# transmitter_SI5351_Arduinol.net
KiCad netlist of a schematic drawn in EAGLE
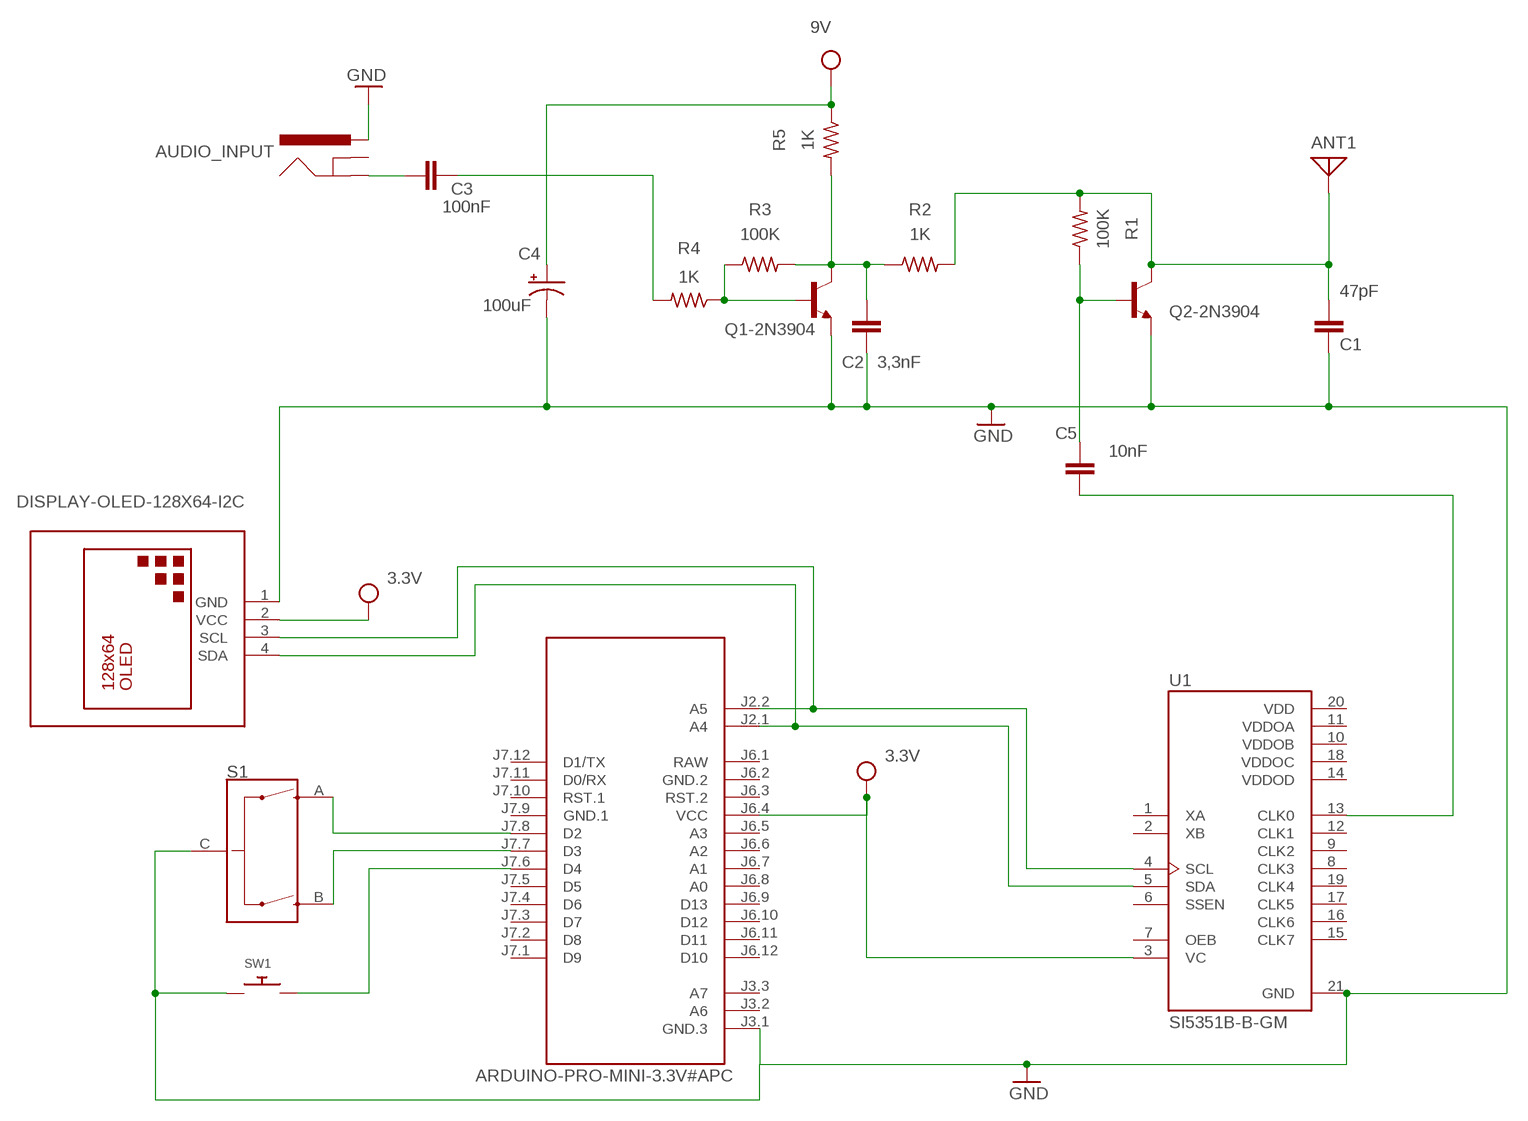
[diagram p0: schematic, sheet 1]

(export (version "E")
  (design (tool "Eeschema 10.0.6"))
  (components
    (comp (ref "ANT1")
      (value "ANTENNA")
      (footprint "eagle-import:PAD-01")
      (libsource (lib "eagle-import") (part "ANTENNA"))
    )
    (comp (ref "AUDIO_INPUT")
      (value "POWER_JACKPTH_SMD_COMBO")
      (footprint "eagle-import:POWER_JACK_COMBO")
      (libsource (lib "eagle-import") (part "POWER_JACKPTH_SMD_COMBO"))
    )
    (comp (ref "C1")
      (value "47pF")
      (footprint "eagle-import:XC10B6")
      (libsource (lib "eagle-import") (part "CXXC10B6"))
    )
    (comp (ref "C2")
      (value "3,3nF")
      (footprint "eagle-import:XC10B6")
      (libsource (lib "eagle-import") (part "CXXC10B6"))
    )
    (comp (ref "C3")
      (value "100nF")
      (footprint "eagle-import:XC10B6")
      (libsource (lib "eagle-import") (part "CXXC10B6"))
    )
    (comp (ref "C4")
      (value "100uF")
      (footprint "eagle-import:NIC_10X10.5_CAP")
      (libsource (lib "eagle-import") (part "100UF-POLAR-10X10.5-63V-20%"))
    )
    (comp (ref "C5")
      (value "10nF")
      (footprint "eagle-import:XC10B6")
      (libsource (lib "eagle-import") (part "CXXC10B6"))
    )
    (comp (ref "M2")
      (value "ARDUINO-PRO-MINI-3.3V#APC")
      (footprint "eagle-import:ARDUINO-PRO-MINI#APC")
      (libsource (lib "eagle-import") (part "ARDUINO-PRO-MINI-#APC3.3V"))
    )
    (comp (ref "Q1-2N3904")
      (value "200mA/40V")
      (footprint "eagle-import:TO-92")
      (libsource (lib "eagle-import") (part "TRANS_NPN-2N3904"))
    )
    (comp (ref "Q2-2N3904")
      (value "200mA/40V")
      (footprint "eagle-import:TO-92")
      (libsource (lib "eagle-import") (part "TRANS_NPN-2N3904"))
    )
    (comp (ref "R1")
      (value "100K")
      (footprint "eagle-import:RESAD724W46L381D178B")
      (libsource (lib "eagle-import") (part "R-USAXIAL-7.2MM-PITCH_"))
    )
    (comp (ref "R2")
      (value "1K")
      (footprint "eagle-import:RESAD724W46L381D178B")
      (libsource (lib "eagle-import") (part "R-USAXIAL-7.2MM-PITCH_"))
    )
    (comp (ref "R3")
      (value "100K")
      (footprint "eagle-import:RESAD724W46L381D178B")
      (libsource (lib "eagle-import") (part "R-USAXIAL-7.2MM-PITCH_"))
    )
    (comp (ref "R4")
      (value "1K")
      (footprint "eagle-import:RESAD724W46L381D178B")
      (libsource (lib "eagle-import") (part "R-USAXIAL-7.2MM-PITCH_"))
    )
    (comp (ref "R5")
      (value "1K")
      (footprint "eagle-import:RESAD724W46L381D178B")
      (libsource (lib "eagle-import") (part "R-USAXIAL-7.2MM-PITCH_"))
    )
    (comp (ref "S1")
      (value "ENCODER")
      (footprint "eagle-import:ENCODER-16MM-QUAD")
      (libsource (lib "eagle-import") (part "ENCODER"))
    )
    (comp (ref "SW1")
      (value "SWITCH_PUSHBUTTONC&K_KSS")
      (footprint "eagle-import:BTN_CK_KSS")
      (libsource (lib "eagle-import") (part "SWITCH_PUSHBUTTONC&K_KSS"))
    )
    (comp (ref "U$2")
      (value "DISPLAY-OLED-128X64-I2C")
      (footprint "eagle-import:DISPLAY-OLED-128X64-I2C")
      (libsource (lib "eagle-import") (part "DISPLAY-OLED-128X64-I2C"))
    )
    (comp (ref "U1")
      (value "SI5351B-B-GM")
      (footprint "eagle-import:QFN50P400X400X90-21N")
      (fields (field (name "MF") "Silicon Labs"))
      (libsource (lib "eagle-import") (part "SI5351B-B-GM"))
    )
  )
  (nets
    (net (code "1") (name "/GND.1") (class "Default")
      (node (ref "M2") (pin "J7.9") (pinfunction "GND.1_J7.9") (pintype "power_in"))
    )
    (net (code "2") (name "/GND.2") (class "Default")
      (node (ref "M2") (pin "J6.2") (pinfunction "GND.2_J6.2") (pintype "power_in"))
    )
    (net (code "3") (name "/RAW") (class "Default")
      (node (ref "M2") (pin "J6.1") (pinfunction "RAW_J6.1") (pintype "power_in"))
    )
    (net (code "4") (name "/VDD") (class "Default")
      (node (ref "U1") (pin "20") (pinfunction "VDD_20") (pintype "power_in"))
    )
    (net (code "5") (name "/VDDOA") (class "Default")
      (node (ref "U1") (pin "11") (pinfunction "VDDOA_11") (pintype "power_in"))
    )
    (net (code "6") (name "/VDDOB") (class "Default")
      (node (ref "U1") (pin "10") (pinfunction "VDDOB_10") (pintype "power_in"))
    )
    (net (code "7") (name "/VDDOC") (class "Default")
      (node (ref "U1") (pin "18") (pinfunction "VDDOC_18") (pintype "power_in"))
    )
    (net (code "8") (name "/VDDOD") (class "Default")
      (node (ref "U1") (pin "14") (pinfunction "VDDOD_14") (pintype "power_in"))
    )
    (net (code "9") (name "GND") (class "Default")
      (node (ref "AUDIO_INPUT") (pin "POWER") (pinfunction "PWR_POWER") (pintype "bidirectional"))
      (node (ref "C1") (pin "2") (pinfunction "2_2") (pintype "passive"))
      (node (ref "C2") (pin "2") (pinfunction "2_2") (pintype "passive"))
      (node (ref "C4") (pin "-") (pinfunction "-_-") (pintype "passive"))
      (node (ref "M2") (pin "J3.1") (pinfunction "GND.3_J3.1") (pintype "bidirectional"))
      (node (ref "Q1-2N3904") (pin "1") (pinfunction "E_1") (pintype "passive"))
      (node (ref "Q2-2N3904") (pin "1") (pinfunction "E_1") (pintype "passive"))
      (node (ref "S1") (pin "C") (pinfunction "C_C") (pintype "bidirectional"))
      (node (ref "SW1") (pin "P$1") (pinfunction "P$1_P$1") (pintype "passive"))
      (node (ref "U$2") (pin "1") (pinfunction "GND_1") (pintype "power_in"))
      (node (ref "U1") (pin "21") (pinfunction "GND_21") (pintype "power_in"))
    )
    (net (code "10") (name "Net-(AUDIO_INPUT-GND)") (class "Default")
      (node (ref "AUDIO_INPUT") (pin "GND@1") (pinfunction "GND_GND@1") (pintype "bidirectional"))
      (node (ref "C3") (pin "1") (pinfunction "1_1") (pintype "passive"))
    )
    (net (code "11") (name "Net-(C3-Pad2)") (class "Default")
      (node (ref "C3") (pin "2") (pinfunction "2_2") (pintype "passive"))
      (node (ref "R4") (pin "2") (pinfunction "2_2") (pintype "passive"))
    )
    (net (code "12") (name "Net-(M2-A4)") (class "Default")
      (node (ref "M2") (pin "J2.1") (pinfunction "A4_J2.1") (pintype "bidirectional"))
      (node (ref "U$2") (pin "4") (pinfunction "SDA_4") (pintype "bidirectional"))
      (node (ref "U1") (pin "5") (pinfunction "SDA_5") (pintype "bidirectional"))
    )
    (net (code "13") (name "Net-(M2-A5)") (class "Default")
      (node (ref "M2") (pin "J2.2") (pinfunction "A5_J2.2") (pintype "bidirectional"))
      (node (ref "U$2") (pin "3") (pinfunction "SCL_3") (pintype "bidirectional"))
      (node (ref "U1") (pin "4") (pinfunction "SCL_4") (pintype "input"))
    )
    (net (code "14") (name "Net-(M2-D2)") (class "Default")
      (node (ref "M2") (pin "J7.8") (pinfunction "D2_J7.8") (pintype "bidirectional"))
      (node (ref "S1") (pin "A") (pinfunction "A_A") (pintype "bidirectional"))
    )
    (net (code "15") (name "Net-(M2-D3)") (class "Default")
      (node (ref "M2") (pin "J7.7") (pinfunction "D3_J7.7") (pintype "bidirectional"))
      (node (ref "S1") (pin "B") (pinfunction "B_B") (pintype "bidirectional"))
    )
    (net (code "16") (name "Net-(M2-D4)") (class "Default")
      (node (ref "M2") (pin "J7.6") (pinfunction "D4_J7.6") (pintype "bidirectional"))
      (node (ref "SW1") (pin "P$2") (pinfunction "P$2_P$2") (pintype "passive"))
    )
    (net (code "17") (name "Net-(Q1-2N3904-B)") (class "Default")
      (node (ref "Q1-2N3904") (pin "2") (pinfunction "B_2") (pintype "passive"))
      (node (ref "R3") (pin "1") (pinfunction "1_1") (pintype "passive"))
      (node (ref "R4") (pin "1") (pinfunction "1_1") (pintype "passive"))
    )
    (net (code "18") (name "Net-(Q1-2N3904-C)") (class "Default")
      (node (ref "C2") (pin "1") (pinfunction "1_1") (pintype "passive"))
      (node (ref "Q1-2N3904") (pin "3") (pinfunction "C_3") (pintype "passive"))
      (node (ref "R2") (pin "1") (pinfunction "1_1") (pintype "passive"))
      (node (ref "R3") (pin "2") (pinfunction "2_2") (pintype "passive"))
      (node (ref "R5") (pin "2") (pinfunction "2_2") (pintype "passive"))
    )
    (net (code "19") (name "Net-(Q2-2N3904-B)") (class "Default")
      (node (ref "C5") (pin "1") (pinfunction "1_1") (pintype "passive"))
      (node (ref "Q2-2N3904") (pin "2") (pinfunction "B_2") (pintype "passive"))
      (node (ref "R1") (pin "1") (pinfunction "1_1") (pintype "passive"))
    )
    (net (code "20") (name "Net-(Q2-2N3904-C)") (class "Default")
      (node (ref "ANT1") (pin "1") (pinfunction "1_1") (pintype "output"))
      (node (ref "C1") (pin "1") (pinfunction "1_1") (pintype "passive"))
      (node (ref "Q2-2N3904") (pin "3") (pinfunction "C_3") (pintype "passive"))
      (node (ref "R1") (pin "2") (pinfunction "2_2") (pintype "passive"))
      (node (ref "R2") (pin "2") (pinfunction "2_2") (pintype "passive"))
    )
    (net (code "21") (name "Net-(U1-CLK0)") (class "Default")
      (node (ref "C5") (pin "2") (pinfunction "2_2") (pintype "passive"))
      (node (ref "U1") (pin "13") (pinfunction "CLK0_13") (pintype "output"))
    )
    (net (code "22") (name "VCC") (class "Default")
      (node (ref "C4") (pin "+") (pinfunction "+_+") (pintype "passive"))
      (node (ref "M2") (pin "J6.4") (pinfunction "VCC_J6.4") (pintype "power_in"))
      (node (ref "R5") (pin "1") (pinfunction "1_1") (pintype "passive"))
      (node (ref "U$2") (pin "2") (pinfunction "VCC_2") (pintype "power_in"))
      (node (ref "U1") (pin "3") (pinfunction "VC_3") (pintype "input"))
    )
    (net (code "23") (name "unconnected-(AUDIO_INPUT-GNDBREAK-PadGND)") (class "Default")
      (node (ref "AUDIO_INPUT") (pin "GND") (pinfunction "GNDBREAK_GND") (pintype "bidirectional"))
    )
    (net (code "24") (name "unconnected-(M2-A0-PadJ6.8)") (class "Default")
      (node (ref "M2") (pin "J6.8") (pinfunction "A0_J6.8") (pintype "bidirectional"))
    )
    (net (code "25") (name "unconnected-(M2-A1-PadJ6.7)") (class "Default")
      (node (ref "M2") (pin "J6.7") (pinfunction "A1_J6.7") (pintype "bidirectional"))
    )
    (net (code "26") (name "unconnected-(M2-A2-PadJ6.6)") (class "Default")
      (node (ref "M2") (pin "J6.6") (pinfunction "A2_J6.6") (pintype "bidirectional"))
    )
    (net (code "27") (name "unconnected-(M2-A3-PadJ6.5)") (class "Default")
      (node (ref "M2") (pin "J6.5") (pinfunction "A3_J6.5") (pintype "bidirectional"))
    )
    (net (code "28") (name "unconnected-(M2-A6-PadJ3.2)") (class "Default")
      (node (ref "M2") (pin "J3.2") (pinfunction "A6_J3.2") (pintype "bidirectional"))
    )
    (net (code "29") (name "unconnected-(M2-A7-PadJ3.3)") (class "Default")
      (node (ref "M2") (pin "J3.3") (pinfunction "A7_J3.3") (pintype "bidirectional"))
    )
    (net (code "30") (name "unconnected-(M2-D0{slash}RX-PadJ7.11)") (class "Default")
      (node (ref "M2") (pin "J7.11") (pinfunction "D0/RX_J7.11") (pintype "bidirectional"))
    )
    (net (code "31") (name "unconnected-(M2-D1{slash}TX-PadJ7.12)") (class "Default")
      (node (ref "M2") (pin "J7.12") (pinfunction "D1/TX_J7.12") (pintype "bidirectional"))
    )
    (net (code "32") (name "unconnected-(M2-D5-PadJ7.5)") (class "Default")
      (node (ref "M2") (pin "J7.5") (pinfunction "D5_J7.5") (pintype "bidirectional"))
    )
    (net (code "33") (name "unconnected-(M2-D6-PadJ7.4)") (class "Default")
      (node (ref "M2") (pin "J7.4") (pinfunction "D6_J7.4") (pintype "bidirectional"))
    )
    (net (code "34") (name "unconnected-(M2-D7-PadJ7.3)") (class "Default")
      (node (ref "M2") (pin "J7.3") (pinfunction "D7_J7.3") (pintype "bidirectional"))
    )
    (net (code "35") (name "unconnected-(M2-D8-PadJ7.2)") (class "Default")
      (node (ref "M2") (pin "J7.2") (pinfunction "D8_J7.2") (pintype "bidirectional"))
    )
    (net (code "36") (name "unconnected-(M2-D9-PadJ7.1)") (class "Default")
      (node (ref "M2") (pin "J7.1") (pinfunction "D9_J7.1") (pintype "bidirectional"))
    )
    (net (code "37") (name "unconnected-(M2-D10-PadJ6.12)") (class "Default")
      (node (ref "M2") (pin "J6.12") (pinfunction "D10_J6.12") (pintype "bidirectional"))
    )
    (net (code "38") (name "unconnected-(M2-D11-PadJ6.11)") (class "Default")
      (node (ref "M2") (pin "J6.11") (pinfunction "D11_J6.11") (pintype "bidirectional"))
    )
    (net (code "39") (name "unconnected-(M2-D12-PadJ6.10)") (class "Default")
      (node (ref "M2") (pin "J6.10") (pinfunction "D12_J6.10") (pintype "bidirectional"))
    )
    (net (code "40") (name "unconnected-(M2-D13-PadJ6.9)") (class "Default")
      (node (ref "M2") (pin "J6.9") (pinfunction "D13_J6.9") (pintype "bidirectional"))
    )
    (net (code "41") (name "unconnected-(M2-RST.1-PadJ7.10)") (class "Default")
      (node (ref "M2") (pin "J7.10") (pinfunction "RST.1_J7.10") (pintype "bidirectional"))
    )
    (net (code "42") (name "unconnected-(M2-RST.2-PadJ6.3)") (class "Default")
      (node (ref "M2") (pin "J6.3") (pinfunction "RST.2_J6.3") (pintype "bidirectional"))
    )
    (net (code "43") (name "unconnected-(U1-CLK1-Pad12)") (class "Default")
      (node (ref "U1") (pin "12") (pinfunction "CLK1_12") (pintype "output"))
    )
    (net (code "44") (name "unconnected-(U1-CLK2-Pad9)") (class "Default")
      (node (ref "U1") (pin "9") (pinfunction "CLK2_9") (pintype "output"))
    )
    (net (code "45") (name "unconnected-(U1-CLK3-Pad8)") (class "Default")
      (node (ref "U1") (pin "8") (pinfunction "CLK3_8") (pintype "output"))
    )
    (net (code "46") (name "unconnected-(U1-CLK4-Pad19)") (class "Default")
      (node (ref "U1") (pin "19") (pinfunction "CLK4_19") (pintype "output"))
    )
    (net (code "47") (name "unconnected-(U1-CLK5-Pad17)") (class "Default")
      (node (ref "U1") (pin "17") (pinfunction "CLK5_17") (pintype "output"))
    )
    (net (code "48") (name "unconnected-(U1-CLK6-Pad16)") (class "Default")
      (node (ref "U1") (pin "16") (pinfunction "CLK6_16") (pintype "output"))
    )
    (net (code "49") (name "unconnected-(U1-CLK7-Pad15)") (class "Default")
      (node (ref "U1") (pin "15") (pinfunction "CLK7_15") (pintype "output"))
    )
    (net (code "50") (name "unconnected-(U1-OEB-Pad7)") (class "Default")
      (node (ref "U1") (pin "7") (pinfunction "OEB_7") (pintype "input"))
    )
    (net (code "51") (name "unconnected-(U1-SSEN-Pad6)") (class "Default")
      (node (ref "U1") (pin "6") (pinfunction "SSEN_6") (pintype "input"))
    )
    (net (code "52") (name "unconnected-(U1-XA-Pad1)") (class "Default")
      (node (ref "U1") (pin "1") (pinfunction "XA_1") (pintype "input"))
    )
    (net (code "53") (name "unconnected-(U1-XB-Pad2)") (class "Default")
      (node (ref "U1") (pin "2") (pinfunction "XB_2") (pintype "input"))
    )
  )
)
